# battery_box.net
KiCad netlist of a schematic drawn in EAGLE
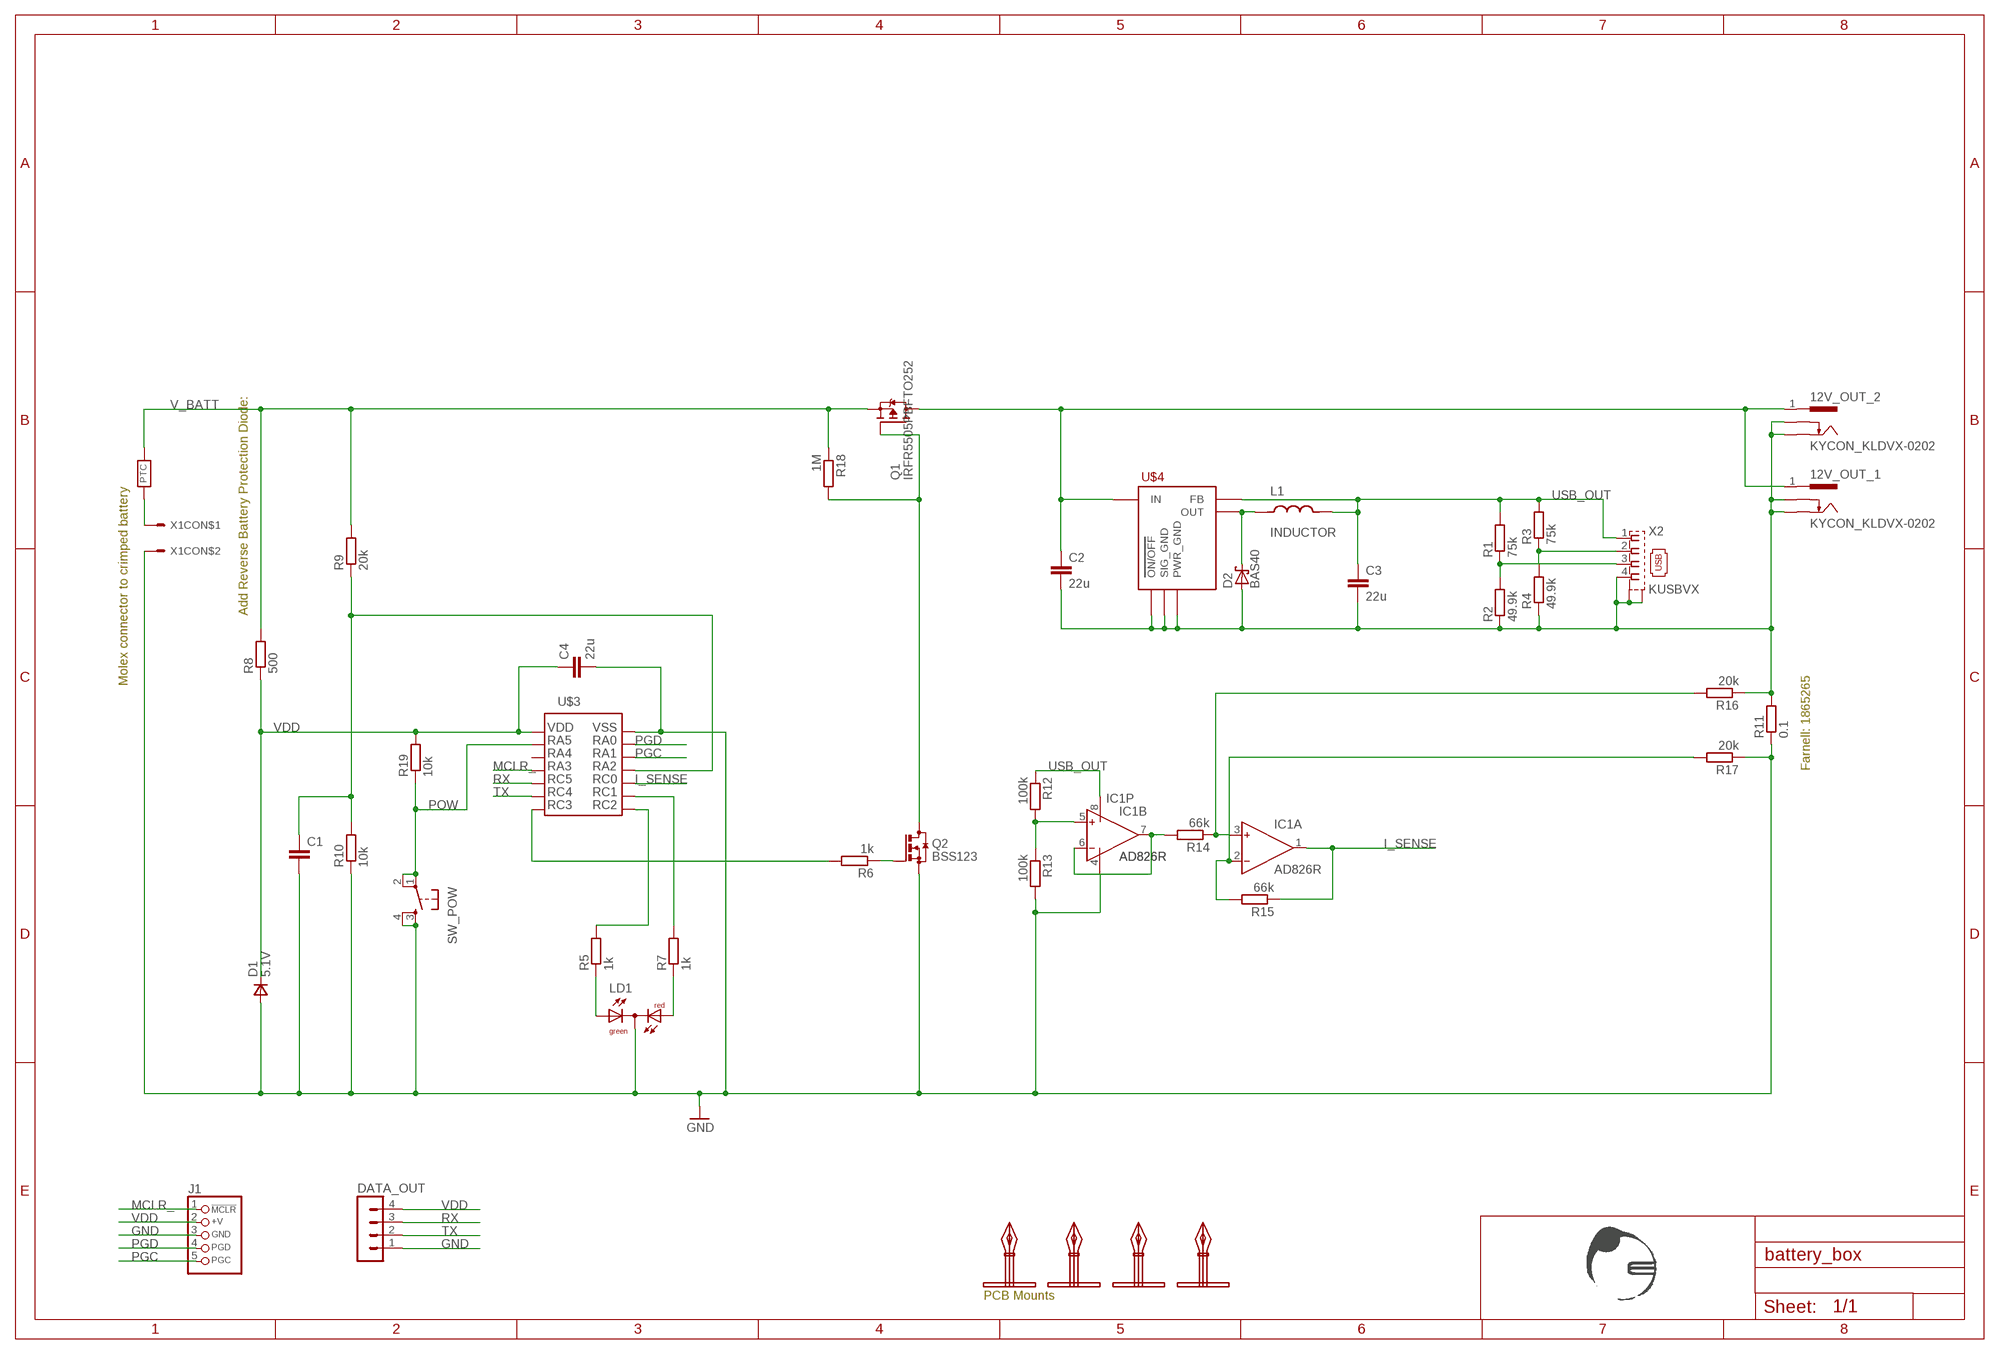
[diagram p0: schematic, sheet 1]

(export (version "E")
  (design (tool "Eeschema 10.0.6"))
  (components
    (comp (ref "12V_OUT_1")
      (value "KYCON_KLDVX-0202")
      (footprint "eagle-import:KYCON_KLVDX_2020_B")
      (libsource (lib "eagle-import") (part "KYCON_KLDVX-0202"))
    )
    (comp (ref "12V_OUT_2")
      (value "KYCON_KLDVX-0202")
      (footprint "eagle-import:KYCON_KLVDX_2020_B")
      (libsource (lib "eagle-import") (part "KYCON_KLDVX-0202"))
    )
    (comp (ref "C1")
      (value "C-EUC0805")
      (footprint "eagle-import:C0805")
      (libsource (lib "eagle-import") (part "C-EUC0805"))
    )
    (comp (ref "C2")
      (value "22u")
      (footprint "eagle-import:C0805")
      (libsource (lib "eagle-import") (part "C-EUC0805"))
    )
    (comp (ref "C3")
      (value "22u")
      (footprint "eagle-import:C0805")
      (libsource (lib "eagle-import") (part "C-EUC0805"))
    )
    (comp (ref "C4")
      (value "22u")
      (footprint "eagle-import:C0805")
      (libsource (lib "eagle-import") (part "C-EUC0805"))
    )
    (comp (ref "D1")
      (value "5.1V")
      (footprint "eagle-import:SOD323")
      (fields (field (name "MPN") "CDSOD323-T05C"))
      (libsource (lib "eagle-import") (part "DSOD323"))
    )
    (comp (ref "D2")
      (value "BAS40")
      (footprint "eagle-import:SOT23")
      (libsource (lib "eagle-import") (part "BAS40"))
    )
    (comp (ref "DATA_OUT")
      (value "MA04-1")
      (footprint "eagle-import:MA04-1")
      (libsource (lib "eagle-import") (part "MA04-1"))
    )
    (comp (ref "IC1")
      (value "AD826R")
      (footprint "eagle-import:SO8")
      (libsource (lib "eagle-import") (part "AD826R"))
    )
    (comp (ref "J1")
      (value "CON_HEADER_PRG_PIC_ICSPA")
      (footprint "eagle-import:HEADER_PRG_1X05")
      (libsource (lib "eagle-import") (part "CON_HEADER_PRG_PIC_ICSPA"))
    )
    (comp (ref "L1")
      (value "INDUCTOR")
      (footprint "eagle-import:SMD_INDUCTOR")
      (libsource (lib "eagle-import") (part "INDUCTOR"))
    )
    (comp (ref "LD1")
      (value "DUOLED-RG-C")
      (footprint "eagle-import:DUOLED-C-5MM")
      (libsource (lib "eagle-import") (part "DUOLED-RG-C"))
    )
    (comp (ref "Q1")
      (value "IRFR5505PBFTO252")
      (footprint "eagle-import:TO252")
      (libsource (lib "eagle-import") (part "IRFR5505PBFTO252"))
    )
    (comp (ref "Q2")
      (value "BSS123")
      (footprint "eagle-import:SOT23")
      (libsource (lib "eagle-import") (part "BSS123"))
    )
    (comp (ref "R1")
      (value "75k")
      (footprint "eagle-import:R0805")
      (libsource (lib "eagle-import") (part "R-EU_R0805"))
    )
    (comp (ref "R2")
      (value "49.9k")
      (footprint "eagle-import:R0805")
      (libsource (lib "eagle-import") (part "R-EU_R0805"))
    )
    (comp (ref "R3")
      (value "75k")
      (footprint "eagle-import:R0805")
      (libsource (lib "eagle-import") (part "R-EU_R0805"))
    )
    (comp (ref "R4")
      (value "49.9k")
      (footprint "eagle-import:R0805")
      (libsource (lib "eagle-import") (part "R-EU_R0805"))
    )
    (comp (ref "R5")
      (value "1k")
      (footprint "eagle-import:R0805")
      (libsource (lib "eagle-import") (part "R-EU_R0805"))
    )
    (comp (ref "R6")
      (value "1k")
      (footprint "eagle-import:R0805")
      (libsource (lib "eagle-import") (part "R-EU_R0805"))
    )
    (comp (ref "R7")
      (value "1k")
      (footprint "eagle-import:R0805")
      (libsource (lib "eagle-import") (part "R-EU_R0805"))
    )
    (comp (ref "R8")
      (value "500")
      (footprint "eagle-import:R0805")
      (libsource (lib "eagle-import") (part "R-EU_R0805"))
    )
    (comp (ref "R9")
      (value "20k")
      (footprint "eagle-import:R0805")
      (libsource (lib "eagle-import") (part "R-EU_R0805"))
    )
    (comp (ref "R10")
      (value "10k")
      (footprint "eagle-import:R0805")
      (libsource (lib "eagle-import") (part "R-EU_R0805"))
    )
    (comp (ref "R11")
      (value "0.1")
      (footprint "eagle-import:R2512")
      (libsource (lib "eagle-import") (part "R-EU_R2512"))
    )
    (comp (ref "R12")
      (value "100k")
      (footprint "eagle-import:R0805")
      (libsource (lib "eagle-import") (part "R-EU_R0805"))
    )
    (comp (ref "R13")
      (value "100k")
      (footprint "eagle-import:R0805")
      (libsource (lib "eagle-import") (part "R-EU_R0805"))
    )
    (comp (ref "R14")
      (value "66k")
      (footprint "eagle-import:R0805")
      (libsource (lib "eagle-import") (part "R-EU_R0805"))
    )
    (comp (ref "R15")
      (value "66k")
      (footprint "eagle-import:R0805")
      (libsource (lib "eagle-import") (part "R-EU_R0805"))
    )
    (comp (ref "R16")
      (value "20k")
      (footprint "eagle-import:R0805")
      (libsource (lib "eagle-import") (part "R-EU_R0805"))
    )
    (comp (ref "R17")
      (value "20k")
      (footprint "eagle-import:R0805")
      (libsource (lib "eagle-import") (part "R-EU_R0805"))
    )
    (comp (ref "R18")
      (value "1M")
      (footprint "eagle-import:R0805")
      (libsource (lib "eagle-import") (part "R-EU_R0805"))
    )
    (comp (ref "R19")
      (value "10k")
      (footprint "eagle-import:R0805")
      (libsource (lib "eagle-import") (part "R-EU_R0805"))
    )
    (comp (ref "SW_POW")
      (value "TAC_SWITCHPTH")
      (footprint "eagle-import:TACTILE-PTH")
      (libsource (lib "eagle-import") (part "TAC_SWITCHPTH"))
    )
    (comp (ref "U$1")
      (value "EQUINOX_LOGO_SMALL")
      (footprint "eagle-import:EQUINOX_LOGO_SMALL")
      (libsource (lib "eagle-import") (part "EQUINOX_LOGO_SMALL"))
    )
    (comp (ref "U$2")
      (value "PTC")
      (footprint "eagle-import:MINISMDC260F")
      (libsource (lib "eagle-import") (part "PTC"))
    )
    (comp (ref "U$3")
      (value "PIC16F1824")
      (footprint "eagle-import:SO-14")
      (libsource (lib "eagle-import") (part "PIC16F1824"))
    )
    (comp (ref "U$4")
      (value "LM2574")
      (footprint "eagle-import:SO14W")
      (libsource (lib "eagle-import") (part "LM2574"))
    )
    (comp (ref "U$5")
      (value "PCB_MOUNT_RICHO")
      (footprint "eagle-import:PCBMOUNT")
      (libsource (lib "eagle-import") (part "PCB_MOUNT_RICHO"))
    )
    (comp (ref "U$6")
      (value "PCB_MOUNT_RICHO")
      (footprint "eagle-import:PCBMOUNT")
      (libsource (lib "eagle-import") (part "PCB_MOUNT_RICHO"))
    )
    (comp (ref "U$7")
      (value "PCB_MOUNT_RICHO")
      (footprint "eagle-import:PCBMOUNT")
      (libsource (lib "eagle-import") (part "PCB_MOUNT_RICHO"))
    )
    (comp (ref "U$8")
      (value "PCB_MOUNT_RICHO")
      (footprint "eagle-import:PCBMOUNT")
      (libsource (lib "eagle-import") (part "PCB_MOUNT_RICHO"))
    )
    (comp (ref "X1")
      (value "CON_MOLEX_39_29_1028")
      (footprint "eagle-import:MOLEX_39_29_1028")
      (libsource (lib "eagle-import") (part "CON_MOLEX_39_29_1028"))
    )
    (comp (ref "X2")
      (value "KUSBVX")
      (footprint "eagle-import:KUSBVX")
      (libsource (lib "eagle-import") (part "KUSBVX"))
    )
  )
  (nets
    (net (code "1") (name "/I_SENSE") (class "Default")
      (node (ref "IC1") (pin "1") (pinfunction "OUT_1") (pintype "output"))
      (node (ref "R15") (pin "1") (pinfunction "1_1") (pintype "passive"))
      (node (ref "U$3") (pin "10") (pinfunction "P$10_10") (pintype "bidirectional"))
    )
    (net (code "2") (name "/MCLR_") (class "Default")
      (node (ref "J1") (pin "1") (pinfunction "/MCLR_1") (pintype "passive"))
      (node (ref "U$3") (pin "4") (pinfunction "P$4_4") (pintype "bidirectional"))
    )
    (net (code "3") (name "/PGC") (class "Default")
      (node (ref "J1") (pin "5") (pinfunction "PGC_5") (pintype "passive"))
      (node (ref "U$3") (pin "12") (pinfunction "P$12_12") (pintype "bidirectional"))
    )
    (net (code "4") (name "/PGD") (class "Default")
      (node (ref "J1") (pin "4") (pinfunction "PGD_4") (pintype "passive"))
      (node (ref "U$3") (pin "13") (pinfunction "P$13_13") (pintype "bidirectional"))
    )
    (net (code "5") (name "/POW") (class "Default")
      (node (ref "R19") (pin "1") (pinfunction "1_1") (pintype "passive"))
      (node (ref "SW_POW") (pin "1") (pinfunction "1_1") (pintype "passive"))
      (node (ref "SW_POW") (pin "2") (pinfunction "2_2") (pintype "passive"))
      (node (ref "U$3") (pin "2") (pinfunction "P$2_2") (pintype "bidirectional"))
    )
    (net (code "6") (name "/RX") (class "Default")
      (node (ref "DATA_OUT") (pin "3") (pinfunction "3_3") (pintype "passive"))
      (node (ref "U$3") (pin "5") (pinfunction "P$5_5") (pintype "bidirectional"))
    )
    (net (code "7") (name "/TX") (class "Default")
      (node (ref "DATA_OUT") (pin "2") (pinfunction "2_2") (pintype "passive"))
      (node (ref "U$3") (pin "6") (pinfunction "P$6_6") (pintype "bidirectional"))
    )
    (net (code "8") (name "/USB_OUT") (class "Default")
      (node (ref "C3") (pin "1") (pinfunction "1_1") (pintype "passive"))
      (node (ref "IC1") (pin "8") (pinfunction "V+_8") (pintype "power_in"))
      (node (ref "L1") (pin "P$2") (pinfunction "P$2_P$2") (pintype "bidirectional"))
      (node (ref "R1") (pin "2") (pinfunction "2_2") (pintype "passive"))
      (node (ref "R12") (pin "1") (pinfunction "1_1") (pintype "passive"))
      (node (ref "R3") (pin "2") (pinfunction "2_2") (pintype "passive"))
      (node (ref "U$4") (pin "3") (pinfunction "FB_3") (pintype "bidirectional"))
      (node (ref "X2") (pin "1") (pinfunction "1_1") (pintype "passive"))
    )
    (net (code "9") (name "/VDD") (class "Default")
      (node (ref "C4") (pin "1") (pinfunction "1_1") (pintype "passive"))
      (node (ref "D1") (pin "1") (pinfunction "C_1") (pintype "passive"))
      (node (ref "DATA_OUT") (pin "4") (pinfunction "4_4") (pintype "passive"))
      (node (ref "J1") (pin "2") (pinfunction "+V_2") (pintype "passive"))
      (node (ref "R19") (pin "2") (pinfunction "2_2") (pintype "passive"))
      (node (ref "R8") (pin "1") (pinfunction "1_1") (pintype "passive"))
      (node (ref "U$3") (pin "1") (pinfunction "P$1_1") (pintype "bidirectional"))
    )
    (net (code "10") (name "/V_BATT") (class "Default")
      (node (ref "Q1") (pin "2") (pinfunction "S_2") (pintype "passive"))
      (node (ref "R18") (pin "1") (pinfunction "1_1") (pintype "passive"))
      (node (ref "R8") (pin "2") (pinfunction "2_2") (pintype "passive"))
      (node (ref "R9") (pin "2") (pinfunction "2_2") (pintype "passive"))
      (node (ref "U$2") (pin "P$2") (pinfunction "P$2_P$2") (pintype "bidirectional"))
    )
    (net (code "11") (name "GND") (class "Default")
      (node (ref "C1") (pin "2") (pinfunction "2_2") (pintype "passive"))
      (node (ref "C4") (pin "2") (pinfunction "2_2") (pintype "passive"))
      (node (ref "D1") (pin "2") (pinfunction "A_2") (pintype "passive"))
      (node (ref "DATA_OUT") (pin "1") (pinfunction "1_1") (pintype "passive"))
      (node (ref "IC1") (pin "4") (pinfunction "V-_4") (pintype "power_in"))
      (node (ref "J1") (pin "3") (pinfunction "GND_3") (pintype "passive"))
      (node (ref "LD1") (pin "C") (pinfunction "C_C") (pintype "passive"))
      (node (ref "Q2") (pin "2") (pinfunction "S_2") (pintype "passive"))
      (node (ref "R10") (pin "1") (pinfunction "1_1") (pintype "passive"))
      (node (ref "R11") (pin "1") (pinfunction "1_1") (pintype "passive"))
      (node (ref "R13") (pin "2") (pinfunction "2_2") (pintype "passive"))
      (node (ref "R17") (pin "1") (pinfunction "1_1") (pintype "passive"))
      (node (ref "SW_POW") (pin "3") (pinfunction "3_3") (pintype "passive"))
      (node (ref "SW_POW") (pin "4") (pinfunction "4_4") (pintype "passive"))
      (node (ref "U$3") (pin "14") (pinfunction "P$14_14") (pintype "bidirectional"))
      (node (ref "X1") (pin "P$2") (pinfunction "S_P$2") (pintype "passive"))
    )
    (net (code "12") (name "Net-(12V_OUT_1-PAD1)") (class "Default")
      (node (ref "12V_OUT_1") (pin "1") (pinfunction "PAD1_1") (pintype "passive"))
      (node (ref "12V_OUT_2") (pin "1") (pinfunction "PAD1_1") (pintype "passive"))
      (node (ref "C2") (pin "1") (pinfunction "1_1") (pintype "passive"))
      (node (ref "Q1") (pin "3") (pinfunction "D_3") (pintype "passive"))
      (node (ref "U$4") (pin "10") (pinfunction "IN_10") (pintype "bidirectional"))
    )
    (net (code "13") (name "Net-(12V_OUT_1-PAD2)") (class "Default")
      (node (ref "12V_OUT_1") (pin "2") (pinfunction "PAD2_2") (pintype "passive"))
      (node (ref "12V_OUT_1") (pin "3") (pinfunction "PAD3_3") (pintype "passive"))
      (node (ref "12V_OUT_2") (pin "2") (pinfunction "PAD2_2") (pintype "passive"))
      (node (ref "12V_OUT_2") (pin "3") (pinfunction "PAD3_3") (pintype "passive"))
      (node (ref "C2") (pin "2") (pinfunction "2_2") (pintype "passive"))
      (node (ref "C3") (pin "2") (pinfunction "2_2") (pintype "passive"))
      (node (ref "D2") (pin "1") (pinfunction "A_1") (pintype "passive"))
      (node (ref "R11") (pin "2") (pinfunction "2_2") (pintype "passive"))
      (node (ref "R16") (pin "1") (pinfunction "1_1") (pintype "passive"))
      (node (ref "R2") (pin "1") (pinfunction "1_1") (pintype "passive"))
      (node (ref "R4") (pin "1") (pinfunction "1_1") (pintype "passive"))
      (node (ref "U$4") (pin "4") (pinfunction "SIG_GND_4") (pintype "bidirectional"))
      (node (ref "U$4") (pin "5") (pinfunction "ON/OFF_5") (pintype "bidirectional"))
      (node (ref "U$4") (pin "6") (pinfunction "PWR_GND_6") (pintype "bidirectional"))
      (node (ref "X2") (pin "4") (pinfunction "4_4") (pintype "passive"))
      (node (ref "X2") (pin "M1") (pinfunction "S1_M1") (pintype "passive"))
      (node (ref "X2") (pin "M2") (pinfunction "S2_M2") (pintype "passive"))
    )
    (net (code "14") (name "Net-(D2-C)") (class "Default")
      (node (ref "D2") (pin "3") (pinfunction "C_3") (pintype "passive"))
      (node (ref "L1") (pin "P$1") (pinfunction "P$1_P$1") (pintype "bidirectional"))
      (node (ref "U$4") (pin "12") (pinfunction "OUT_12") (pintype "bidirectional"))
    )
    (net (code "15") (name "Net-(IC1A-IN+)") (class "Default")
      (node (ref "IC1") (pin "3") (pinfunction "IN+_3") (pintype "input"))
      (node (ref "R14") (pin "1") (pinfunction "1_1") (pintype "passive"))
      (node (ref "R16") (pin "2") (pinfunction "2_2") (pintype "passive"))
    )
    (net (code "16") (name "Net-(IC1A-IN-)") (class "Default")
      (node (ref "IC1") (pin "2") (pinfunction "IN-_2") (pintype "input"))
      (node (ref "R15") (pin "2") (pinfunction "2_2") (pintype "passive"))
      (node (ref "R17") (pin "2") (pinfunction "2_2") (pintype "passive"))
    )
    (net (code "17") (name "Net-(IC1B-IN+)") (class "Default")
      (node (ref "IC1") (pin "5") (pinfunction "IN+_5") (pintype "input"))
      (node (ref "R12") (pin "2") (pinfunction "2_2") (pintype "passive"))
      (node (ref "R13") (pin "1") (pinfunction "1_1") (pintype "passive"))
    )
    (net (code "18") (name "Net-(IC1B-IN-)") (class "Default")
      (node (ref "IC1") (pin "6") (pinfunction "IN-_6") (pintype "input"))
      (node (ref "IC1") (pin "7") (pinfunction "OUT_7") (pintype "output"))
      (node (ref "R14") (pin "2") (pinfunction "2_2") (pintype "passive"))
    )
    (net (code "19") (name "Net-(LD1-AG)") (class "Default")
      (node (ref "LD1") (pin "AX") (pinfunction "AG_AX") (pintype "passive"))
      (node (ref "R5") (pin "1") (pinfunction "1_1") (pintype "passive"))
    )
    (net (code "20") (name "Net-(LD1-PadAR)") (class "Default")
      (node (ref "LD1") (pin "AR") (pinfunction "AR_AR") (pintype "passive"))
      (node (ref "R7") (pin "1") (pinfunction "1_1") (pintype "passive"))
    )
    (net (code "21") (name "Net-(Q1-G)") (class "Default")
      (node (ref "Q1") (pin "1") (pinfunction "G_1") (pintype "passive"))
      (node (ref "Q2") (pin "3") (pinfunction "D_3") (pintype "passive"))
      (node (ref "R18") (pin "2") (pinfunction "2_2") (pintype "passive"))
    )
    (net (code "22") (name "Net-(Q2-G)") (class "Default")
      (node (ref "Q2") (pin "1") (pinfunction "G_1") (pintype "passive"))
      (node (ref "R6") (pin "1") (pinfunction "1_1") (pintype "passive"))
    )
    (net (code "23") (name "Net-(R1-Pad1)") (class "Default")
      (node (ref "R1") (pin "1") (pinfunction "1_1") (pintype "passive"))
      (node (ref "R2") (pin "2") (pinfunction "2_2") (pintype "passive"))
      (node (ref "X2") (pin "3") (pinfunction "3_3") (pintype "passive"))
    )
    (net (code "24") (name "Net-(R3-Pad1)") (class "Default")
      (node (ref "R3") (pin "1") (pinfunction "1_1") (pintype "passive"))
      (node (ref "R4") (pin "2") (pinfunction "2_2") (pintype "passive"))
      (node (ref "X2") (pin "2") (pinfunction "2_2") (pintype "passive"))
    )
    (net (code "25") (name "Net-(U$3-P$7)") (class "Default")
      (node (ref "R6") (pin "2") (pinfunction "2_2") (pintype "passive"))
      (node (ref "U$3") (pin "7") (pinfunction "P$7_7") (pintype "bidirectional"))
    )
    (net (code "26") (name "Net-(U$3-P$8)") (class "Default")
      (node (ref "R5") (pin "2") (pinfunction "2_2") (pintype "passive"))
      (node (ref "U$3") (pin "8") (pinfunction "P$8_8") (pintype "bidirectional"))
    )
    (net (code "27") (name "Net-(U$3-P$9)") (class "Default")
      (node (ref "R7") (pin "2") (pinfunction "2_2") (pintype "passive"))
      (node (ref "U$3") (pin "9") (pinfunction "P$9_9") (pintype "bidirectional"))
    )
    (net (code "28") (name "Net-(U$3-P$11)") (class "Default")
      (node (ref "C1") (pin "1") (pinfunction "1_1") (pintype "passive"))
      (node (ref "R10") (pin "2") (pinfunction "2_2") (pintype "passive"))
      (node (ref "R9") (pin "1") (pinfunction "1_1") (pintype "passive"))
      (node (ref "U$3") (pin "11") (pinfunction "P$11_11") (pintype "bidirectional"))
    )
    (net (code "29") (name "Net-(X1A-S)") (class "Default")
      (node (ref "U$2") (pin "P$1") (pinfunction "P$1_P$1") (pintype "bidirectional"))
      (node (ref "X1") (pin "P$1") (pinfunction "S_P$1") (pintype "passive"))
    )
    (net (code "30") (name "unconnected-(U$3-P$3-Pad3)") (class "Default")
      (node (ref "U$3") (pin "3") (pinfunction "P$3_3") (pintype "bidirectional"))
    )
  )
)
